# Halloween2017.net
KiCad netlist of a schematic drawn in EAGLE
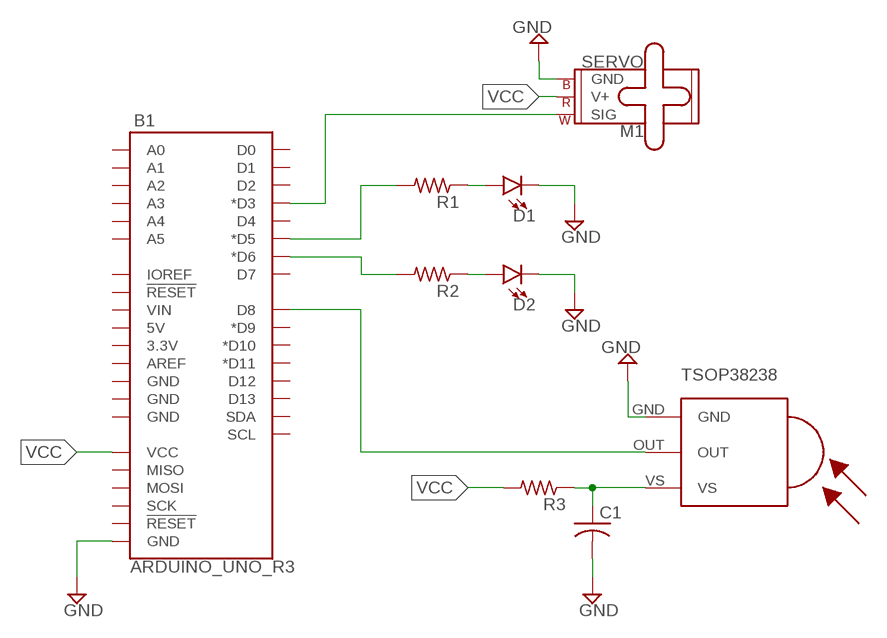
[diagram p0: schematic, sheet 1]

(export (version "E")
  (design (tool "Eeschema 10.0.6"))
  (components
    (comp (ref "B1")
      (value "ARDUINO_UNO_R3")
      (footprint "eagle-import:ARDUINO_R3")
      (libsource (lib "eagle-import") (part "ARDUINO_UNO_R3"))
    )
    (comp (ref "C1")
      (value "C-US025-040X050")
      (footprint "eagle-import:C025-040X050")
      (libsource (lib "eagle-import") (part "C-US025-040X050"))
    )
    (comp (ref "D1")
      (value "LED5MM")
      (footprint "eagle-import:LED_5MM")
      (libsource (lib "eagle-import") (part "LED5MM"))
    )
    (comp (ref "D2")
      (value "LED5MM")
      (footprint "eagle-import:LED_5MM")
      (libsource (lib "eagle-import") (part "LED5MM"))
    )
    (comp (ref "M1")
      (value "SERVO")
      (footprint "eagle-import:1X03")
      (libsource (lib "eagle-import") (part "SERVO"))
    )
    (comp (ref "R1")
      (value "R-US_0309/10")
      (footprint "eagle-import:0309_10")
      (libsource (lib "eagle-import") (part "R-US_0309/10"))
    )
    (comp (ref "R2")
      (value "R-US_0309/10")
      (footprint "eagle-import:0309_10")
      (libsource (lib "eagle-import") (part "R-US_0309/10"))
    )
    (comp (ref "R3")
      (value "R-US_0309/10")
      (footprint "eagle-import:0309_10")
      (libsource (lib "eagle-import") (part "R-US_0309/10"))
    )
    (comp (ref "TSOP38238")
      (value "TSOP38238")
      (footprint "eagle-import:TSOP-382")
      (fields (field (name "MF") "Vishay") (field (name "MP") "TSOP38238"))
      (libsource (lib "eagle-import") (part "TSOP38238"))
    )
  )
  (nets
    (net (code "1") (name "GND") (class "Default")
      (node (ref "B1") (pin "GND@1") (pinfunction "GND_GND@1") (pintype "bidirectional"))
      (node (ref "C1") (pin "2") (pinfunction "2_2") (pintype "passive"))
      (node (ref "D1") (pin "K") (pinfunction "C_K") (pintype "passive"))
      (node (ref "D2") (pin "K") (pinfunction "C_K") (pintype "passive"))
      (node (ref "M1") (pin "3") (pinfunction "GND_3") (pintype "bidirectional"))
      (node (ref "TSOP38238") (pin "GND") (pinfunction "GND_GND") (pintype "bidirectional"))
    )
    (net (code "2") (name "Net-(B1-*D3)") (class "Default")
      (node (ref "B1") (pin "D3") (pinfunction "*D3_D3") (pintype "bidirectional"))
      (node (ref "M1") (pin "1") (pinfunction "SIG_1") (pintype "bidirectional"))
    )
    (net (code "3") (name "Net-(B1-*D5)") (class "Default")
      (node (ref "B1") (pin "D5") (pinfunction "*D5_D5") (pintype "bidirectional"))
      (node (ref "R1") (pin "2") (pinfunction "2_2") (pintype "passive"))
    )
    (net (code "4") (name "Net-(B1-*D6)") (class "Default")
      (node (ref "B1") (pin "D6") (pinfunction "*D6_D6") (pintype "bidirectional"))
      (node (ref "R2") (pin "2") (pinfunction "2_2") (pintype "passive"))
    )
    (net (code "5") (name "Net-(B1-PadD8)") (class "Default")
      (node (ref "B1") (pin "D8") (pinfunction "D8_D8") (pintype "bidirectional"))
      (node (ref "TSOP38238") (pin "OUT") (pinfunction "OUT_OUT") (pintype "bidirectional"))
    )
    (net (code "6") (name "Net-(C1-Pad1)") (class "Default")
      (node (ref "C1") (pin "1") (pinfunction "1_1") (pintype "passive"))
      (node (ref "R3") (pin "1") (pinfunction "1_1") (pintype "passive"))
      (node (ref "TSOP38238") (pin "VS") (pinfunction "VS_VS") (pintype "bidirectional"))
    )
    (net (code "7") (name "Net-(D1-PadA)") (class "Default")
      (node (ref "D1") (pin "A") (pinfunction "A_A") (pintype "passive"))
      (node (ref "R1") (pin "1") (pinfunction "1_1") (pintype "passive"))
    )
    (net (code "8") (name "Net-(D2-PadA)") (class "Default")
      (node (ref "D2") (pin "A") (pinfunction "A_A") (pintype "passive"))
      (node (ref "R2") (pin "1") (pinfunction "1_1") (pintype "passive"))
    )
    (net (code "9") (name "VCC") (class "Default")
      (node (ref "B1") (pin "VCC") (pinfunction "VCC_VCC") (pintype "bidirectional"))
      (node (ref "M1") (pin "2") (pinfunction "V+_2") (pintype "bidirectional"))
      (node (ref "R3") (pin "2") (pinfunction "2_2") (pintype "passive"))
    )
    (net (code "10") (name "unconnected-(B1-*D9-PadD9)") (class "Default")
      (node (ref "B1") (pin "D9") (pinfunction "*D9_D9") (pintype "bidirectional"))
    )
    (net (code "11") (name "unconnected-(B1-*D10-PadD10)") (class "Default")
      (node (ref "B1") (pin "D10") (pinfunction "*D10_D10") (pintype "bidirectional"))
    )
    (net (code "12") (name "unconnected-(B1-*D11-PadD11)") (class "Default")
      (node (ref "B1") (pin "D11") (pinfunction "*D11_D11") (pintype "bidirectional"))
    )
    (net (code "13") (name "unconnected-(B1-GND-PadGND@2)") (class "Default")
      (node (ref "B1") (pin "GND@2") (pinfunction "GND_GND@2") (pintype "bidirectional"))
    )
    (net (code "14") (name "unconnected-(B1-GND-PadGND@3)") (class "Default")
      (node (ref "B1") (pin "GND@3") (pinfunction "GND_GND@3") (pintype "bidirectional"))
    )
    (net (code "15") (name "unconnected-(B1-GND-PadGND@4)") (class "Default")
      (node (ref "B1") (pin "GND@4") (pinfunction "GND_GND@4") (pintype "bidirectional"))
    )
    (net (code "16") (name "unconnected-(B1-Pad3.3V)") (class "Default")
      (node (ref "B1") (pin "3.3V") (pinfunction "3.3V_3.3V") (pintype "bidirectional"))
    )
    (net (code "17") (name "unconnected-(B1-Pad5V)") (class "Default")
      (node (ref "B1") (pin "5V") (pinfunction "5V_5V") (pintype "bidirectional"))
    )
    (net (code "18") (name "unconnected-(B1-PadA0)") (class "Default")
      (node (ref "B1") (pin "A0") (pinfunction "A0_A0") (pintype "bidirectional"))
    )
    (net (code "19") (name "unconnected-(B1-PadA1)") (class "Default")
      (node (ref "B1") (pin "A1") (pinfunction "A1_A1") (pintype "bidirectional"))
    )
    (net (code "20") (name "unconnected-(B1-PadA2)") (class "Default")
      (node (ref "B1") (pin "A2") (pinfunction "A2_A2") (pintype "bidirectional"))
    )
    (net (code "21") (name "unconnected-(B1-PadA3)") (class "Default")
      (node (ref "B1") (pin "A3") (pinfunction "A3_A3") (pintype "bidirectional"))
    )
    (net (code "22") (name "unconnected-(B1-PadA4)") (class "Default")
      (node (ref "B1") (pin "A4") (pinfunction "A4_A4") (pintype "bidirectional"))
    )
    (net (code "23") (name "unconnected-(B1-PadA5)") (class "Default")
      (node (ref "B1") (pin "A5") (pinfunction "A5_A5") (pintype "bidirectional"))
    )
    (net (code "24") (name "unconnected-(B1-PadAREF)") (class "Default")
      (node (ref "B1") (pin "AREF") (pinfunction "AREF_AREF") (pintype "bidirectional"))
    )
    (net (code "25") (name "unconnected-(B1-PadD0)") (class "Default")
      (node (ref "B1") (pin "D0") (pinfunction "D0_D0") (pintype "bidirectional"))
    )
    (net (code "26") (name "unconnected-(B1-PadD1)") (class "Default")
      (node (ref "B1") (pin "D1") (pinfunction "D1_D1") (pintype "bidirectional"))
    )
    (net (code "27") (name "unconnected-(B1-PadD2)") (class "Default")
      (node (ref "B1") (pin "D2") (pinfunction "D2_D2") (pintype "bidirectional"))
    )
    (net (code "28") (name "unconnected-(B1-PadD4)") (class "Default")
      (node (ref "B1") (pin "D4") (pinfunction "D4_D4") (pintype "bidirectional"))
    )
    (net (code "29") (name "unconnected-(B1-PadD7)") (class "Default")
      (node (ref "B1") (pin "D7") (pinfunction "D7_D7") (pintype "bidirectional"))
    )
    (net (code "30") (name "unconnected-(B1-PadD12)") (class "Default")
      (node (ref "B1") (pin "D12") (pinfunction "D12_D12") (pintype "bidirectional"))
    )
    (net (code "31") (name "unconnected-(B1-PadD13)") (class "Default")
      (node (ref "B1") (pin "D13") (pinfunction "D13_D13") (pintype "bidirectional"))
    )
    (net (code "32") (name "unconnected-(B1-PadIOREF)") (class "Default")
      (node (ref "B1") (pin "IOREF") (pinfunction "IOREF_IOREF") (pintype "bidirectional"))
    )
    (net (code "33") (name "unconnected-(B1-PadMISO)") (class "Default")
      (node (ref "B1") (pin "MISO") (pinfunction "MISO_MISO") (pintype "bidirectional"))
    )
    (net (code "34") (name "unconnected-(B1-PadMOSI)") (class "Default")
      (node (ref "B1") (pin "MOSI") (pinfunction "MOSI_MOSI") (pintype "bidirectional"))
    )
    (net (code "35") (name "unconnected-(B1-PadSCK)") (class "Default")
      (node (ref "B1") (pin "SCK") (pinfunction "SCK_SCK") (pintype "bidirectional"))
    )
    (net (code "36") (name "unconnected-(B1-PadSCL)") (class "Default")
      (node (ref "B1") (pin "SCL") (pinfunction "SCL_SCL") (pintype "bidirectional"))
    )
    (net (code "37") (name "unconnected-(B1-PadSDA)") (class "Default")
      (node (ref "B1") (pin "SDA") (pinfunction "SDA_SDA") (pintype "bidirectional"))
    )
    (net (code "38") (name "unconnected-(B1-PadVIN)") (class "Default")
      (node (ref "B1") (pin "VIN") (pinfunction "VIN_VIN") (pintype "bidirectional"))
    )
    (net (code "39") (name "unconnected-(B1-~{RESET}-PadRESET@1)") (class "Default")
      (node (ref "B1") (pin "RESET@1") (pinfunction "~{RESET}_RESET@1") (pintype "bidirectional"))
    )
    (net (code "40") (name "unconnected-(B1-~{RESET}-PadRESET@2)") (class "Default")
      (node (ref "B1") (pin "RESET@2") (pinfunction "~{RESET}_RESET@2") (pintype "bidirectional"))
    )
  )
)
